# leicester_rev_A.net
KiCad netlist of a schematic drawn in EAGLE
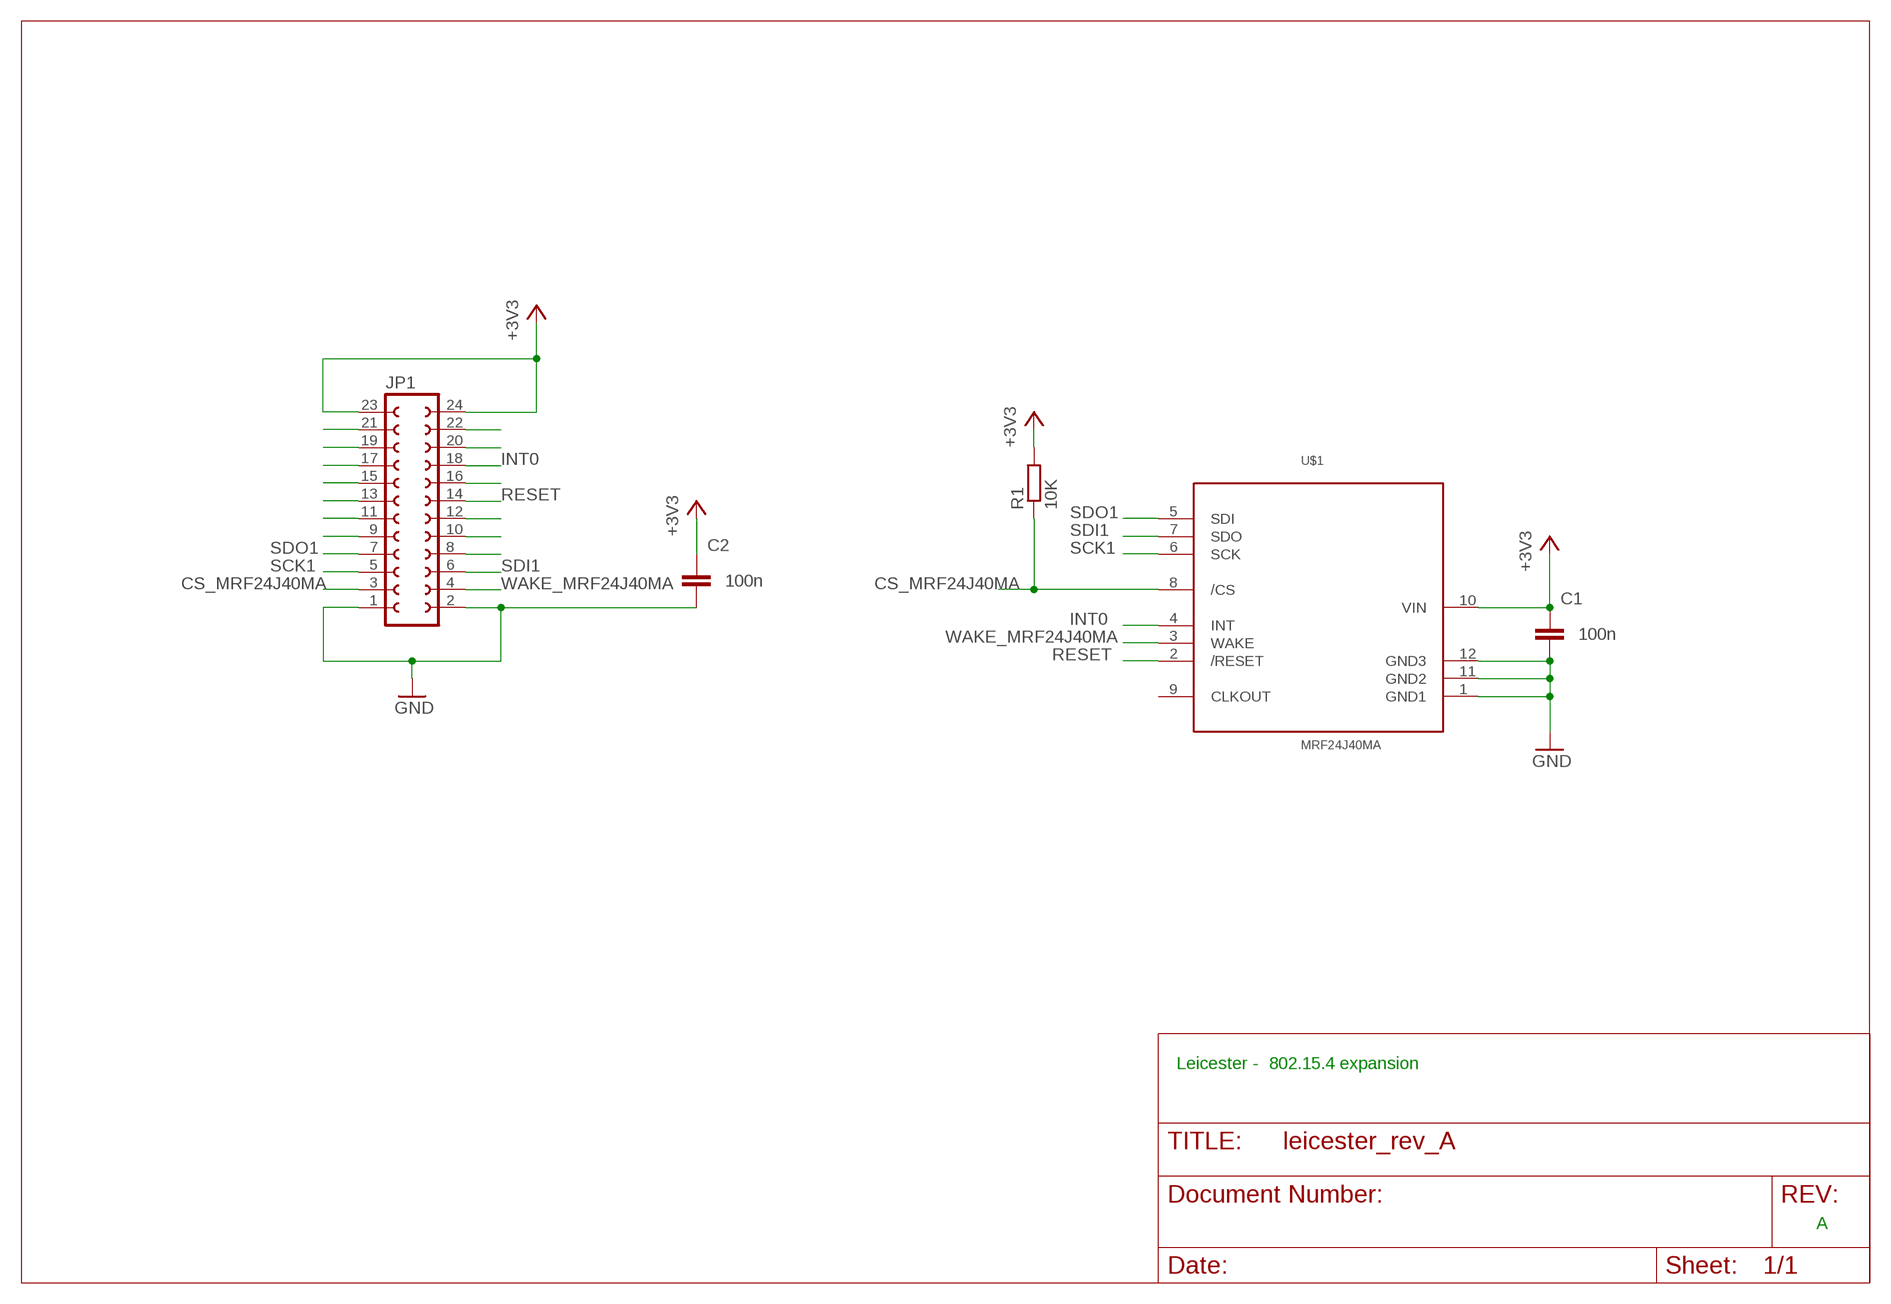
[diagram p0: schematic, sheet 1]

(export (version "E")
  (design (tool "Eeschema 10.0.6"))
  (components
    (comp (ref "C1")
      (value "100n")
      (footprint "eagle-import:C0805")
      (libsource (lib "eagle-import") (part "C-EUC0805"))
    )
    (comp (ref "C2")
      (value "100n")
      (footprint "eagle-import:C0805")
      (libsource (lib "eagle-import") (part "C-EUC0805"))
    )
    (comp (ref "JP1")
      (value "FE12-2")
      (footprint "eagle-import:FE12-2")
      (libsource (lib "eagle-import") (part "FE12-2"))
    )
    (comp (ref "R1")
      (value "10K")
      (footprint "eagle-import:R0805")
      (libsource (lib "eagle-import") (part "R-EU_R0805"))
    )
    (comp (ref "U$1")
      (value "MRF24J40MA")
      (footprint "eagle-import:MRF24J40MA")
      (libsource (lib "eagle-import") (part "MRF24J40MA"))
    )
  )
  (nets
    (net (code "1") (name "+3V3") (class "Default")
      (node (ref "C1") (pin "1") (pinfunction "1_1") (pintype "passive"))
      (node (ref "C2") (pin "1") (pinfunction "1_1") (pintype "passive"))
      (node (ref "JP1") (pin "23") (pinfunction "23_23") (pintype "passive"))
      (node (ref "JP1") (pin "24") (pinfunction "24_24") (pintype "passive"))
      (node (ref "R1") (pin "2") (pinfunction "2_2") (pintype "passive"))
      (node (ref "U$1") (pin "10") (pinfunction "VIN_10") (pintype "power_in"))
    )
    (net (code "2") (name "/CS_MRF24J40MA") (class "Default")
      (node (ref "JP1") (pin "3") (pinfunction "3_3") (pintype "passive"))
      (node (ref "R1") (pin "1") (pinfunction "1_1") (pintype "passive"))
      (node (ref "U$1") (pin "8") (pinfunction "/CS_8") (pintype "bidirectional"))
    )
    (net (code "3") (name "/INT0") (class "Default")
      (node (ref "JP1") (pin "18") (pinfunction "18_18") (pintype "passive"))
      (node (ref "U$1") (pin "4") (pinfunction "INT_4") (pintype "bidirectional"))
    )
    (net (code "4") (name "/RESET") (class "Default")
      (node (ref "JP1") (pin "14") (pinfunction "14_14") (pintype "passive"))
      (node (ref "U$1") (pin "2") (pinfunction "/RESET_2") (pintype "bidirectional"))
    )
    (net (code "5") (name "/SCK1") (class "Default")
      (node (ref "JP1") (pin "5") (pinfunction "5_5") (pintype "passive"))
      (node (ref "U$1") (pin "6") (pinfunction "SCK_6") (pintype "bidirectional"))
    )
    (net (code "6") (name "/SDI1") (class "Default")
      (node (ref "JP1") (pin "6") (pinfunction "6_6") (pintype "passive"))
      (node (ref "U$1") (pin "7") (pinfunction "SDO_7") (pintype "bidirectional"))
    )
    (net (code "7") (name "/SDO1") (class "Default")
      (node (ref "JP1") (pin "7") (pinfunction "7_7") (pintype "passive"))
      (node (ref "U$1") (pin "5") (pinfunction "SDI_5") (pintype "bidirectional"))
    )
    (net (code "8") (name "/WAKE_MRF24J40MA") (class "Default")
      (node (ref "JP1") (pin "4") (pinfunction "4_4") (pintype "passive"))
      (node (ref "U$1") (pin "3") (pinfunction "WAKE_3") (pintype "bidirectional"))
    )
    (net (code "9") (name "GND") (class "Default")
      (node (ref "C1") (pin "2") (pinfunction "2_2") (pintype "passive"))
      (node (ref "C2") (pin "2") (pinfunction "2_2") (pintype "passive"))
      (node (ref "JP1") (pin "1") (pinfunction "1_1") (pintype "passive"))
      (node (ref "JP1") (pin "2") (pinfunction "2_2") (pintype "passive"))
      (node (ref "U$1") (pin "1") (pinfunction "GND1_1") (pintype "power_in"))
      (node (ref "U$1") (pin "11") (pinfunction "GND2_11") (pintype "power_in"))
      (node (ref "U$1") (pin "12") (pinfunction "GND3_12") (pintype "power_in"))
    )
    (net (code "10") (name "unconnected-(JP1-Pad8)") (class "Default")
      (node (ref "JP1") (pin "8") (pinfunction "8_8") (pintype "passive"))
    )
    (net (code "11") (name "unconnected-(JP1-Pad9)") (class "Default")
      (node (ref "JP1") (pin "9") (pinfunction "9_9") (pintype "passive"))
    )
    (net (code "12") (name "unconnected-(JP1-Pad10)") (class "Default")
      (node (ref "JP1") (pin "10") (pinfunction "10_10") (pintype "passive"))
    )
    (net (code "13") (name "unconnected-(JP1-Pad11)") (class "Default")
      (node (ref "JP1") (pin "11") (pinfunction "11_11") (pintype "passive"))
    )
    (net (code "14") (name "unconnected-(JP1-Pad12)") (class "Default")
      (node (ref "JP1") (pin "12") (pinfunction "12_12") (pintype "passive"))
    )
    (net (code "15") (name "unconnected-(JP1-Pad13)") (class "Default")
      (node (ref "JP1") (pin "13") (pinfunction "13_13") (pintype "passive"))
    )
    (net (code "16") (name "unconnected-(JP1-Pad15)") (class "Default")
      (node (ref "JP1") (pin "15") (pinfunction "15_15") (pintype "passive"))
    )
    (net (code "17") (name "unconnected-(JP1-Pad16)") (class "Default")
      (node (ref "JP1") (pin "16") (pinfunction "16_16") (pintype "passive"))
    )
    (net (code "18") (name "unconnected-(JP1-Pad17)") (class "Default")
      (node (ref "JP1") (pin "17") (pinfunction "17_17") (pintype "passive"))
    )
    (net (code "19") (name "unconnected-(JP1-Pad19)") (class "Default")
      (node (ref "JP1") (pin "19") (pinfunction "19_19") (pintype "passive"))
    )
    (net (code "20") (name "unconnected-(JP1-Pad20)") (class "Default")
      (node (ref "JP1") (pin "20") (pinfunction "20_20") (pintype "passive"))
    )
    (net (code "21") (name "unconnected-(JP1-Pad21)") (class "Default")
      (node (ref "JP1") (pin "21") (pinfunction "21_21") (pintype "passive"))
    )
    (net (code "22") (name "unconnected-(JP1-Pad22)") (class "Default")
      (node (ref "JP1") (pin "22") (pinfunction "22_22") (pintype "passive"))
    )
    (net (code "23") (name "unconnected-(U$1-CLKOUT-Pad9)") (class "Default")
      (node (ref "U$1") (pin "9") (pinfunction "CLKOUT_9") (pintype "output"))
    )
  )
)
